# IMU_SCH.net
KiCad netlist of a schematic drawn in Altium Designer
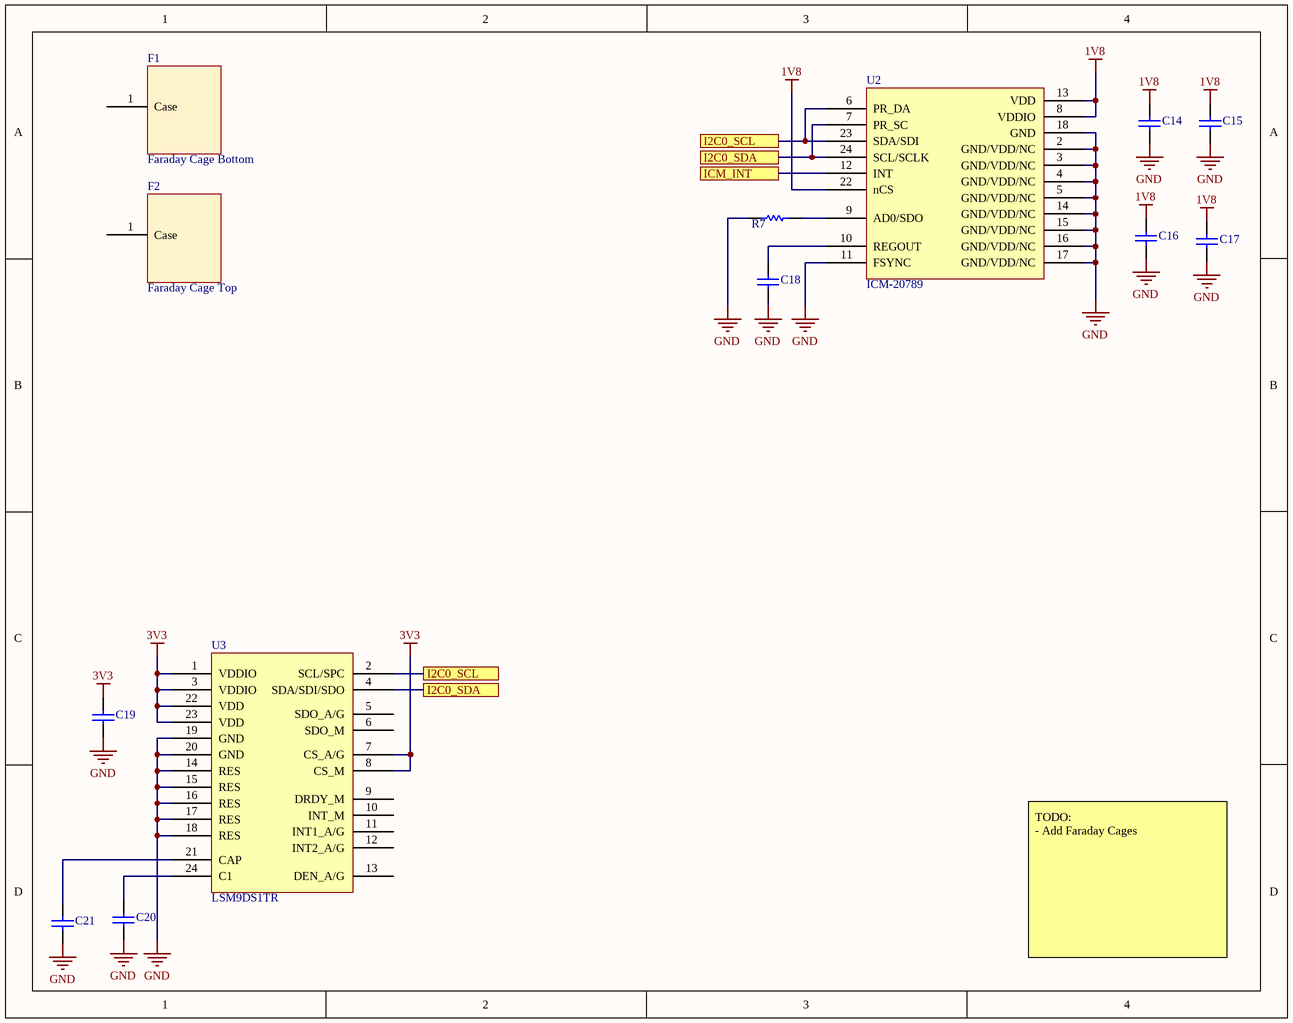
[diagram p0: IMU_SCH.SchDoc]

(export (version "E")
  (design (tool "Eeschema 10.0.6"))
  (components
    (comp (ref "C14")
      (value "08055C104KAJ2A")
      (footprint "CAPC2013X140X50NL20T25")
      (fields (field (name "MANUFACTURER") "AVX Interconnect / Elco"))
      (libsource (lib "Altium Content Vault") (part "CAP"))
    )
    (comp (ref "C15")
      (value "08055C104KAJ2A")
      (footprint "CAPC2013X140X50NL20T25")
      (fields (field (name "MANUFACTURER") "AVX Interconnect / Elco"))
      (libsource (lib "Altium Content Vault") (part "CAP"))
    )
    (comp (ref "C16")
      (value "08055C104KAJ2A")
      (footprint "CAPC2013X140X50NL20T25")
      (fields (field (name "MANUFACTURER") "AVX Interconnect / Elco"))
      (libsource (lib "Altium Content Vault") (part "CAP"))
    )
    (comp (ref "C17")
      (value "08055C104KAJ2A")
      (footprint "CAPC2013X140X50NL20T25")
      (fields (field (name "MANUFACTURER") "AVX Interconnect / Elco"))
      (libsource (lib "Altium Content Vault") (part "CAP"))
    )
    (comp (ref "C18")
      (value "08055C104KAJ2A")
      (footprint "CAPC2013X140X50NL20T25")
      (fields (field (name "MANUFACTURER") "AVX Interconnect / Elco"))
      (libsource (lib "Altium Content Vault") (part "CAP"))
    )
    (comp (ref "C19")
      (value "08055C104KAJ2A")
      (footprint "CAPC2013X140X50NL20T25")
      (fields (field (name "MANUFACTURER") "AVX Interconnect / Elco"))
      (libsource (lib "Altium Content Vault") (part "CAP"))
    )
    (comp (ref "C20")
      (value "08055C104KAJ2A")
      (footprint "CAPC2013X140X50NL20T25")
      (fields (field (name "MANUFACTURER") "AVX Interconnect / Elco"))
      (libsource (lib "Altium Content Vault") (part "CAP"))
    )
    (comp (ref "C21")
      (value "08055C104KAJ2A")
      (footprint "CAPC2013X140X50NL20T25")
      (fields (field (name "MANUFACTURER") "AVX Interconnect / Elco"))
      (libsource (lib "Altium Content Vault") (part "CAP"))
    )
    (comp (ref "F1") (value "Faraday Cage Bottom") (libsource (lib "Copter") (part "FARADAY_CAGE")))
    (comp (ref "F2") (value "Faraday Cage Top") (libsource (lib "Copter") (part "FARADAY_CAGE")))
    (comp (ref "R7")
      (value "ERJ-6ENF1503V")
      (footprint "RESC2013X70X40LL20T20")
      (description "RES SMD 150K OHM 1% 1/8W 0805")
      (fields (field (name "MANUFACTURER") "Panasonic"))
      (libsource (lib "Altium Content Vault") (part "RES"))
    )
    (comp (ref "U2")
      (value "ICM-20789")
      (footprint "24LGA")
      (description "MOTION SENSOR IC")
      (libsource (lib "Copter") (part "ICM-20789"))
    )
    (comp (ref "U3")
      (value "LSM9DS1TR")
      (footprint "24LGA_Elongated")
      (description "IMU ACCEL/GYRO/MAG I2C/SPI 24LGA")
      (libsource (lib "Copter") (part "LSM9DS1TR"))
    )
  )
  (nets
    (net (code "1") (name "/I2C0_SCL") (class "Default")
      (node (ref "U2") (pin "23") (pinfunction "SDA/SDI_23") (pintype "passive"))
      (node (ref "U2") (pin "6") (pinfunction "PR_DA_6") (pintype "passive"))
      (node (ref "U3") (pin "2") (pinfunction "SCL/SPC_2") (pintype "passive"))
    )
    (net (code "2") (name "/I2C0_SDA") (class "Default")
      (node (ref "U2") (pin "24") (pinfunction "SCL/SCLK_24") (pintype "passive"))
      (node (ref "U2") (pin "7") (pinfunction "PR_SC_7") (pintype "passive"))
      (node (ref "U3") (pin "4") (pinfunction "SDA/SDI/SDO_4") (pintype "passive"))
    )
    (net (code "3") (name "/ICM_INT") (class "Default")
      (node (ref "U2") (pin "12") (pinfunction "INT_12") (pintype "passive"))
    )
    (net (code "4") (name "1V8") (class "Default")
      (node (ref "C14") (pin "2") (pinfunction "2_2") (pintype "passive"))
      (node (ref "C15") (pin "2") (pinfunction "2_2") (pintype "passive"))
      (node (ref "C16") (pin "2") (pinfunction "2_2") (pintype "passive"))
      (node (ref "C17") (pin "2") (pinfunction "2_2") (pintype "passive"))
      (node (ref "U2") (pin "13") (pinfunction "VDD_13") (pintype "passive"))
      (node (ref "U2") (pin "22") (pinfunction "nCS_22") (pintype "passive"))
      (node (ref "U2") (pin "8") (pinfunction "VDDIO_8") (pintype "passive"))
    )
    (net (code "5") (name "3V3") (class "Default")
      (node (ref "C19") (pin "2") (pinfunction "2_2") (pintype "passive"))
      (node (ref "U3") (pin "1") (pinfunction "VDDIO_1") (pintype "passive"))
      (node (ref "U3") (pin "22") (pinfunction "VDD_22") (pintype "passive"))
      (node (ref "U3") (pin "23") (pinfunction "VDD_23") (pintype "passive"))
      (node (ref "U3") (pin "3") (pinfunction "VDDIO_3") (pintype "passive"))
      (node (ref "U3") (pin "7") (pinfunction "CS_A/G_7") (pintype "passive"))
      (node (ref "U3") (pin "8") (pinfunction "CS_M_8") (pintype "passive"))
    )
    (net (code "6") (name "GND") (class "Default")
      (node (ref "C14") (pin "1") (pinfunction "1_1") (pintype "passive"))
      (node (ref "C15") (pin "1") (pinfunction "1_1") (pintype "passive"))
      (node (ref "C16") (pin "1") (pinfunction "1_1") (pintype "passive"))
      (node (ref "C17") (pin "1") (pinfunction "1_1") (pintype "passive"))
      (node (ref "C18") (pin "1") (pinfunction "1_1") (pintype "passive"))
      (node (ref "C19") (pin "1") (pinfunction "1_1") (pintype "passive"))
      (node (ref "C20") (pin "1") (pinfunction "1_1") (pintype "passive"))
      (node (ref "C21") (pin "1") (pinfunction "1_1") (pintype "passive"))
      (node (ref "R7") (pin "1") (pinfunction "1_1") (pintype "passive"))
      (node (ref "U2") (pin "11") (pinfunction "FSYNC_11") (pintype "passive"))
      (node (ref "U2") (pin "14") (pinfunction "GND/VDD/NC_14") (pintype "passive"))
      (node (ref "U2") (pin "15") (pinfunction "GND/VDD/NC_15") (pintype "passive"))
      (node (ref "U2") (pin "16") (pinfunction "GND/VDD/NC_16") (pintype "passive"))
      (node (ref "U2") (pin "17") (pinfunction "GND/VDD/NC_17") (pintype "passive"))
      (node (ref "U2") (pin "18") (pinfunction "GND_18") (pintype "passive"))
      (node (ref "U2") (pin "2") (pinfunction "GND/VDD/NC_2") (pintype "passive"))
      (node (ref "U2") (pin "3") (pinfunction "GND/VDD/NC_3") (pintype "passive"))
      (node (ref "U2") (pin "4") (pinfunction "GND/VDD/NC_4") (pintype "passive"))
      (node (ref "U2") (pin "5") (pinfunction "GND/VDD/NC_5") (pintype "passive"))
      (node (ref "U3") (pin "14") (pinfunction "RES_14") (pintype "passive"))
      (node (ref "U3") (pin "15") (pinfunction "RES_15") (pintype "passive"))
      (node (ref "U3") (pin "16") (pinfunction "RES_16") (pintype "passive"))
      (node (ref "U3") (pin "17") (pinfunction "RES_17") (pintype "passive"))
      (node (ref "U3") (pin "18") (pinfunction "RES_18") (pintype "passive"))
      (node (ref "U3") (pin "19") (pinfunction "GND_19") (pintype "passive"))
      (node (ref "U3") (pin "20") (pinfunction "GND_20") (pintype "passive"))
    )
    (net (code "7") (name "Net-(U2-AD0{slash}SDO)") (class "Default")
      (node (ref "R7") (pin "2") (pinfunction "2_2") (pintype "passive"))
      (node (ref "U2") (pin "9") (pinfunction "AD0/SDO_9") (pintype "passive"))
    )
    (net (code "8") (name "Net-(U2-REGOUT)") (class "Default")
      (node (ref "C18") (pin "2") (pinfunction "2_2") (pintype "passive"))
      (node (ref "U2") (pin "10") (pinfunction "REGOUT_10") (pintype "passive"))
    )
    (net (code "9") (name "Net-(U3-C1)") (class "Default")
      (node (ref "C20") (pin "2") (pinfunction "2_2") (pintype "passive"))
      (node (ref "U3") (pin "24") (pinfunction "C1_24") (pintype "passive"))
    )
    (net (code "10") (name "Net-(U3-CAP)") (class "Default")
      (node (ref "C21") (pin "2") (pinfunction "2_2") (pintype "passive"))
      (node (ref "U3") (pin "21") (pinfunction "CAP_21") (pintype "passive"))
    )
    (net (code "11") (name "unconnected-(F1-Case-Pad1)") (class "Default")
      (node (ref "F1") (pin "1") (pinfunction "Case_1") (pintype "passive"))
    )
    (net (code "12") (name "unconnected-(F2-Case-Pad1)") (class "Default")
      (node (ref "F2") (pin "1") (pinfunction "Case_1") (pintype "passive"))
    )
    (net (code "13") (name "unconnected-(U3-DEN_A{slash}G-Pad13)") (class "Default")
      (node (ref "U3") (pin "13") (pinfunction "DEN_A/G_13") (pintype "passive"))
    )
    (net (code "14") (name "unconnected-(U3-DRDY_M-Pad9)") (class "Default")
      (node (ref "U3") (pin "9") (pinfunction "DRDY_M_9") (pintype "passive"))
    )
    (net (code "15") (name "unconnected-(U3-INT1_A{slash}G-Pad11)") (class "Default")
      (node (ref "U3") (pin "11") (pinfunction "INT1_A/G_11") (pintype "passive"))
    )
    (net (code "16") (name "unconnected-(U3-INT2_A{slash}G-Pad12)") (class "Default")
      (node (ref "U3") (pin "12") (pinfunction "INT2_A/G_12") (pintype "passive"))
    )
    (net (code "17") (name "unconnected-(U3-INT_M-Pad10)") (class "Default")
      (node (ref "U3") (pin "10") (pinfunction "INT_M_10") (pintype "passive"))
    )
    (net (code "18") (name "unconnected-(U3-SDO_A{slash}G-Pad5)") (class "Default")
      (node (ref "U3") (pin "5") (pinfunction "SDO_A/G_5") (pintype "passive"))
    )
    (net (code "19") (name "unconnected-(U3-SDO_M-Pad6)") (class "Default")
      (node (ref "U3") (pin "6") (pinfunction "SDO_M_6") (pintype "passive"))
    )
  )
)
